# secondcompletion.net
KiCad netlist of a schematic drawn in EAGLE
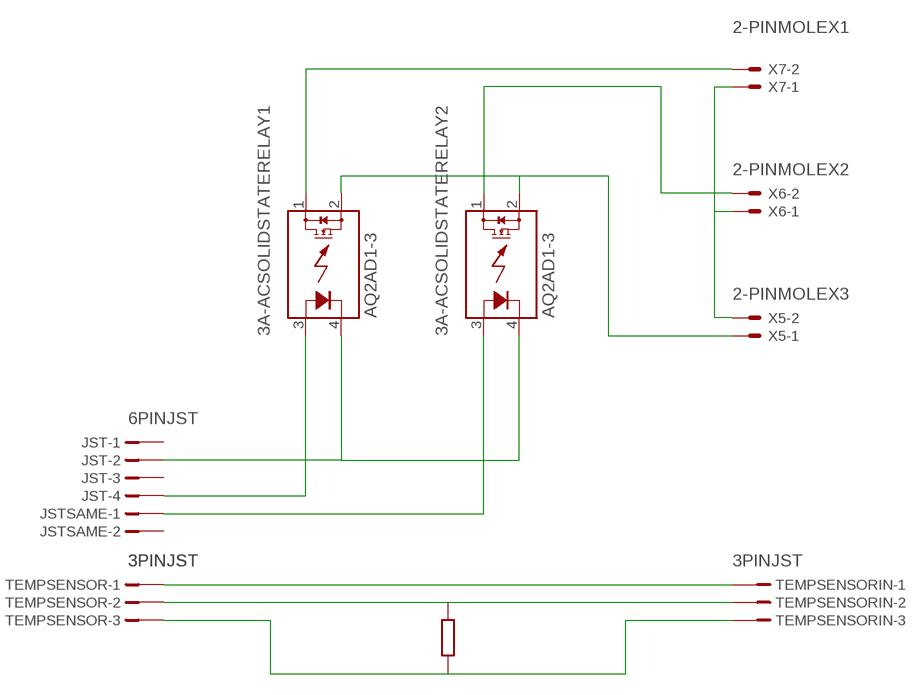
[diagram p0: schematic, sheet 1]

(export (version "E")
  (design (tool "Eeschema 10.0.6"))
  (components
    (comp (ref "JST")
      (value "B4B-ZR")
      (footprint "eagle-import:B4B-ZR")
      (fields (field (name "MF") "FARNELL") (field (name "MPN") "B4B-ZR(LF)(SN)"))
      (libsource (lib "eagle-import") (part "?4B-ZRB"))
    )
    (comp (ref "JSTSAME")
      (value "B4B-ZR")
      (footprint "eagle-import:B4B-ZR")
      (fields (field (name "MF") "FARNELL") (field (name "MPN") "B4B-ZR(LF)(SN)"))
      (libsource (lib "eagle-import") (part "?4B-ZRB"))
    )
    (comp (ref "K1")
      (value "AQ2AD1-3")
      (footprint "eagle-import:AQ1")
      (fields (field (name "MPN") "AQ2AD1-3/28VDC"))
      (libsource (lib "eagle-import") (part "AQ2AD1-3"))
    )
    (comp (ref "K2")
      (value "AQ2AD1-3")
      (footprint "eagle-import:AQ1")
      (fields (field (name "MPN") "AQ2AD1-3/28VDC"))
      (libsource (lib "eagle-import") (part "AQ2AD1-3"))
    )
    (comp (ref "TEMPSENSOR")
      (value "B4B-ZR")
      (footprint "eagle-import:B4B-ZR")
      (fields (field (name "MF") "FARNELL") (field (name "MPN") "B4B-ZR(LF)(SN)"))
      (libsource (lib "eagle-import") (part "?4B-ZRB"))
    )
    (comp (ref "TEMPSENSORIN")
      (value "B4B-ZR")
      (footprint "eagle-import:B4B-ZR")
      (fields (field (name "MF") "FARNELL") (field (name "MPN") "B4B-ZR(LF)(SN)"))
      (libsource (lib "eagle-import") (part "?4B-ZRB"))
    )
    (comp (ref "X5")
      (value "22-23-2021")
      (footprint "eagle-import:22-23-2021")
      (fields (field (name "MF") "MOLEX"))
      (libsource (lib "eagle-import") (part "22-23-2021"))
    )
    (comp (ref "X6")
      (value "22-23-2021")
      (footprint "eagle-import:22-23-2021")
      (fields (field (name "MF") "MOLEX"))
      (libsource (lib "eagle-import") (part "22-23-2021"))
    )
    (comp (ref "X7")
      (value "22-23-2021")
      (footprint "eagle-import:22-23-2021")
      (fields (field (name "MF") "MOLEX"))
      (libsource (lib "eagle-import") (part "22-23-2021"))
    )
  )
  (nets
    (net (code "1") (name "/2-PINMOLEX1") (class "Default")
      (node (ref "K1") (pin "1") (pinfunction "DS1_1") (pintype "passive"))
      (node (ref "X7") (pin "2") (pinfunction "S_2") (pintype "passive"))
    )
    (net (code "2") (name "/2-PINMOLEX2") (class "Default")
      (node (ref "K2") (pin "1") (pinfunction "DS1_1") (pintype "passive"))
      (node (ref "X6") (pin "2") (pinfunction "S_2") (pintype "passive"))
    )
    (net (code "3") (name "/2-PINMOLEX3") (class "Default")
      (node (ref "X5") (pin "2") (pinfunction "S_2") (pintype "passive"))
      (node (ref "X6") (pin "1") (pinfunction "S_1") (pintype "passive"))
      (node (ref "X7") (pin "1") (pinfunction "S_1") (pintype "passive"))
    )
    (net (code "4") (name "/3A-ACSOLIDSTATERELAY1") (class "Default")
      (node (ref "JST") (pin "4") (pinfunction "1_4") (pintype "passive"))
      (node (ref "K1") (pin "3") (pinfunction "A_3") (pintype "passive"))
    )
    (net (code "5") (name "/3A-ACSOLIDSTATERELAY2") (class "Default")
      (node (ref "JSTSAME") (pin "1") (pinfunction "1_1") (pintype "passive"))
      (node (ref "K2") (pin "3") (pinfunction "A_3") (pintype "passive"))
    )
    (net (code "6") (name "/3PINJST") (class "Default")
      (node (ref "TEMPSENSOR") (pin "1") (pinfunction "1_1") (pintype "passive"))
      (node (ref "TEMPSENSORIN") (pin "1") (pinfunction "1_1") (pintype "passive"))
    )
    (net (code "7") (name "/6PINJST") (class "Default")
      (node (ref "JST") (pin "2") (pinfunction "1_2") (pintype "passive"))
      (node (ref "K1") (pin "4") (pinfunction "K_4") (pintype "passive"))
      (node (ref "K2") (pin "4") (pinfunction "K_4") (pintype "passive"))
    )
    (net (code "8") (name "Net-(K1-DS2)") (class "Default")
      (node (ref "K1") (pin "2") (pinfunction "DS2_2") (pintype "passive"))
      (node (ref "K2") (pin "2") (pinfunction "DS2_2") (pintype "passive"))
      (node (ref "X5") (pin "1") (pinfunction "S_1") (pintype "passive"))
    )
    (net (code "9") (name "Net-(TEMPSENSORB-1)") (class "Default")
      (node (ref "TEMPSENSOR") (pin "2") (pinfunction "1_2") (pintype "passive"))
      (node (ref "TEMPSENSORIN") (pin "2") (pinfunction "1_2") (pintype "passive"))
    )
    (net (code "10") (name "Net-(TEMPSENSORC-1)") (class "Default")
      (node (ref "TEMPSENSOR") (pin "3") (pinfunction "1_3") (pintype "passive"))
      (node (ref "TEMPSENSORIN") (pin "3") (pinfunction "1_3") (pintype "passive"))
    )
    (net (code "11") (name "unconnected-(JST-Pad1)") (class "Default")
      (node (ref "JST") (pin "1") (pinfunction "1_1") (pintype "passive"))
    )
    (net (code "12") (name "unconnected-(JSTC-1-Pad3)") (class "Default")
      (node (ref "JST") (pin "3") (pinfunction "1_3") (pintype "passive"))
    )
    (net (code "13") (name "unconnected-(JSTSAMEB-1-Pad2)") (class "Default")
      (node (ref "JSTSAME") (pin "2") (pinfunction "1_2") (pintype "passive"))
    )
  )
)
